# core.net
KiCad netlist of a schematic drawn in Altium Designer
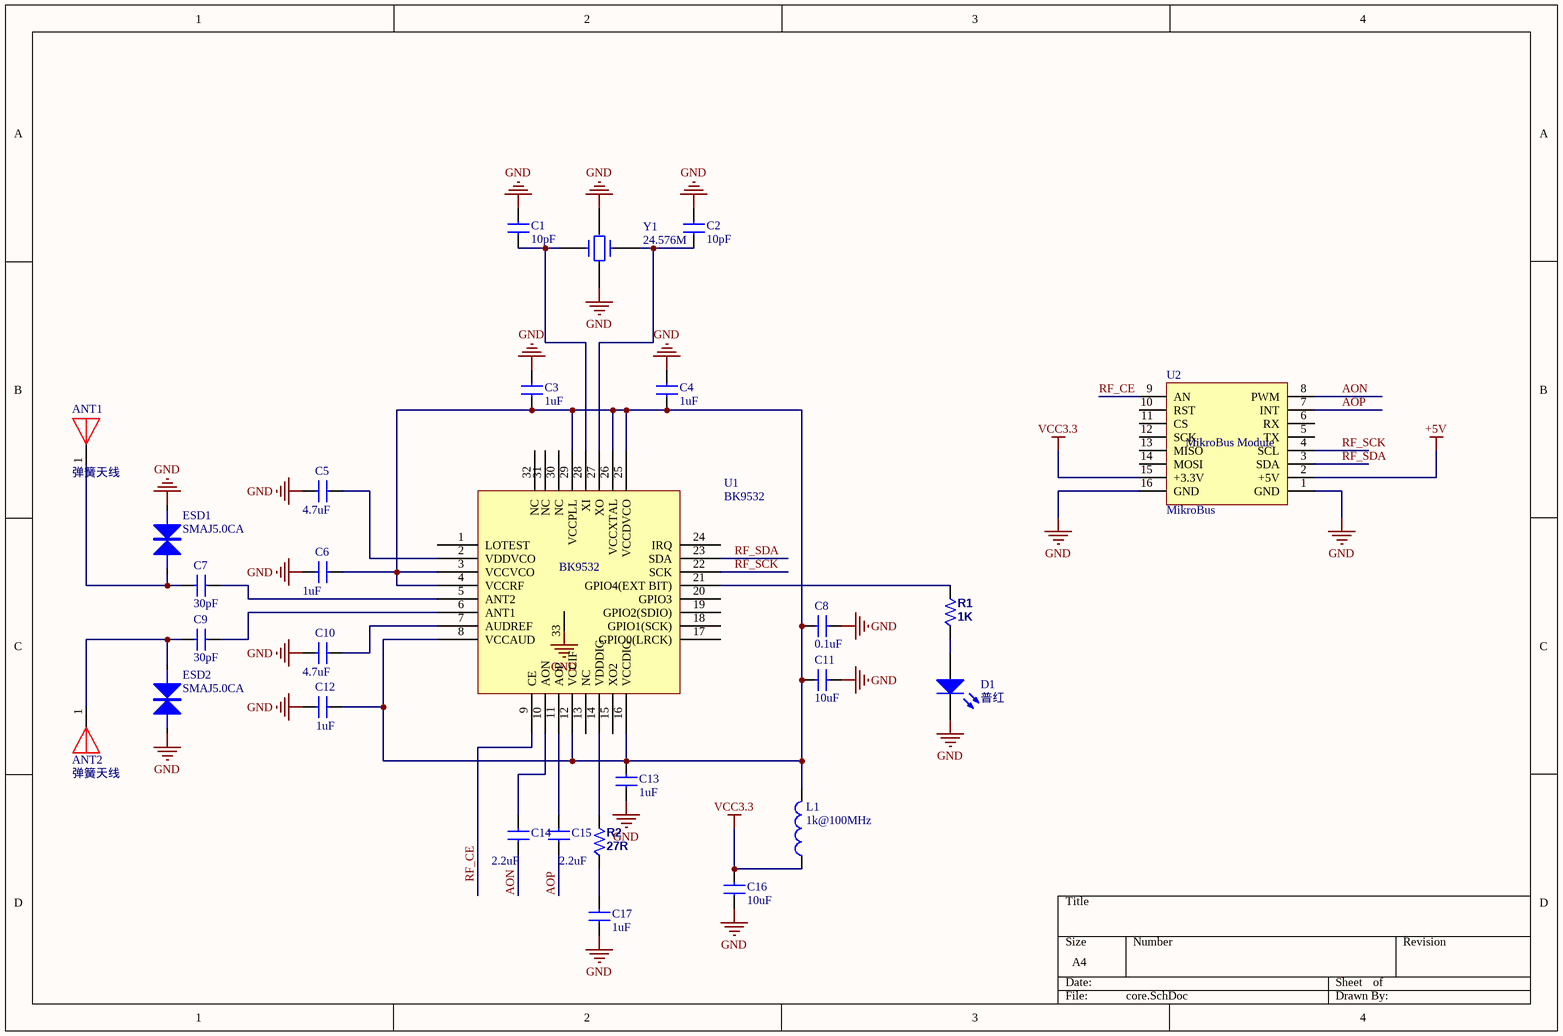
[diagram p0: core.SchDoc]

(export (version "E")
  (design (tool "Eeschema 10.0.6"))
  (components
    (comp (ref "ANT1")
      (value "弹簧天线")
      (footprint "ANT")
      (description "ANT")
      (libsource (lib "二极管") (part "ANT"))
    )
    (comp (ref "ANT2")
      (value "弹簧天线")
      (footprint "ANT")
      (description "ANT")
      (libsource (lib "二极管") (part "ANT"))
    )
    (comp (ref "C1")
      (value "10pF")
      (footprint "C0603")
      (description "0603-10pF/50V 贴片层叠电容")
      (libsource (lib "兰格封装") (part "CAP 0603-10pF/50V"))
    )
    (comp (ref "C2")
      (value "10pF")
      (footprint "C0603")
      (description "0603-10pF/50V 贴片层叠电容")
      (libsource (lib "兰格封装") (part "CAP 0603-10pF/50V"))
    )
    (comp (ref "C3")
      (value "1uF")
      (footprint "C0603")
      (description "0805-68pF/50V-J5%贴片层叠电容")
      (libsource (lib "兰格封装") (part "CAP 0805-68pF/50V"))
    )
    (comp (ref "C4")
      (value "1uF")
      (footprint "C0603")
      (description "0805-68pF/50V-J5%贴片层叠电容")
      (libsource (lib "兰格封装") (part "CAP 0805-68pF/50V"))
    )
    (comp (ref "C5")
      (value "4.7uF")
      (footprint "C0603")
      (description "0805-68pF/50V-J5%贴片层叠电容")
      (libsource (lib "兰格封装") (part "CAP 0805-68pF/50V"))
    )
    (comp (ref "C6")
      (value "1uF")
      (footprint "C0603")
      (description "0805-68pF/50V-J5%贴片层叠电容")
      (libsource (lib "兰格封装") (part "CAP 0805-68pF/50V"))
    )
    (comp (ref "C7")
      (value "30pF")
      (footprint "C0603")
      (description "0603-33pF/50V   贴片层叠电容")
      (libsource (lib "兰格封装") (part "CAP 0603-33pF/50V"))
    )
    (comp (ref "C8")
      (value "0.1uF")
      (footprint "C0603")
      (description "0805-68pF/50V-J5%贴片层叠电容")
      (libsource (lib "兰格封装") (part "CAP 0805-68pF/50V"))
    )
    (comp (ref "C9")
      (value "30pF")
      (footprint "C0603")
      (description "0603-33pF/50V   贴片层叠电容")
      (libsource (lib "兰格封装") (part "CAP 0603-33pF/50V"))
    )
    (comp (ref "C10")
      (value "4.7uF")
      (footprint "C0603")
      (description "0805-68pF/50V-J5%贴片层叠电容")
      (libsource (lib "兰格封装") (part "CAP 0805-68pF/50V"))
    )
    (comp (ref "C11")
      (value "10uF")
      (footprint "C0603")
      (description "0805-68pF/50V-J5%贴片层叠电容")
      (libsource (lib "兰格封装") (part "CAP 0805-68pF/50V"))
    )
    (comp (ref "C12")
      (value "1uF")
      (footprint "C0603")
      (description "0805-68pF/50V-J5%贴片层叠电容")
      (libsource (lib "兰格封装") (part "CAP 0805-68pF/50V"))
    )
    (comp (ref "C13")
      (value "1uF")
      (footprint "C0603")
      (description "0805-68pF/50V-J5%贴片层叠电容")
      (libsource (lib "兰格封装") (part "CAP 0805-68pF/50V"))
    )
    (comp (ref "C14")
      (value "2.2uF")
      (footprint "C0603")
      (description "0805-68pF/50V-J5%贴片层叠电容")
      (libsource (lib "兰格封装") (part "CAP 0805-68pF/50V"))
    )
    (comp (ref "C15")
      (value "2.2uF")
      (footprint "C0603")
      (description "0805-68pF/50V-J5%贴片层叠电容")
      (libsource (lib "兰格封装") (part "CAP 0805-68pF/50V"))
    )
    (comp (ref "C16")
      (value "10uF")
      (footprint "C0603")
      (description "0805-68pF/50V-J5%贴片层叠电容")
      (libsource (lib "兰格封装") (part "CAP 0805-68pF/50V"))
    )
    (comp (ref "C17")
      (value "1uF")
      (footprint "C0603")
      (description "0805-68pF/50V-J5%贴片层叠电容")
      (libsource (lib "兰格封装") (part "CAP 0805-68pF/50V"))
    )
    (comp (ref "D1")
      (value "普红")
      (footprint "LED 0805")
      (description "0805普亮贴片红灯")
      (libsource (lib "兰格封装") (part "LED  0805普亮贴片红灯"))
    )
    (comp (ref "ESD1")
      (value "SMAJ5.0CA")
      (footprint "SMAJ")
      (description "ESD 二极管")
      (libsource (lib "二极管") (part "ESD 防浪涌二极管"))
    )
    (comp (ref "ESD2")
      (value "SMAJ5.0CA")
      (footprint "SMAJ")
      (description "ESD 二极管")
      (libsource (lib "二极管") (part "ESD 防浪涌二极管"))
    )
    (comp (ref "L1")
      (value "1k@100MHz")
      (footprint "L0603")
      (description "磁珠")
      (libsource (lib "兰格封装") (part "电感  贴片  33UH"))
    )
    (comp (ref "R1")
      (value "1K")
      (footprint "R0603")
      (description "1206  K  5%  HS  贴片电阻")
      (libsource (lib "兰格封装") (part "RES1"))
    )
    (comp (ref "R2")
      (value "27R")
      (footprint "R0603")
      (description "1206  K  5%  HS  贴片电阻")
      (libsource (lib "兰格封装") (part "RES1"))
    )
    (comp (ref "U1")
      (value "BK9532")
      (footprint "QFN32")
      (description "QFN5x5 32")
      (libsource (lib "集成IC") (part "BK9532"))
    )
    (comp (ref "U2") (value "MikroBus") (footprint "MikroBus") (libsource (lib "集成IC") (part "MikroBus")))
    (comp (ref "Y1")
      (value "24.576M")
      (footprint "晶振   有源2520")
      (description "（未入库）24.576MHz  2520")
      (libsource (lib "晶体") (part "晶振  24.576MHz  49SMD"))
    )
  )
  (nets
    (net (code "1") (name "+5V") (class "Default")
      (node (ref "U2") (pin "2") (pinfunction "+5V_2") (pintype "passive"))
    )
    (net (code "2") (name "/AON") (class "Default")
      (node (ref "C14") (pin "1") (pinfunction "1_1") (pintype "passive"))
      (node (ref "U2") (pin "8") (pinfunction "PWM_8") (pintype "passive"))
    )
    (net (code "3") (name "/AOP") (class "Default")
      (node (ref "C15") (pin "1") (pinfunction "1_1") (pintype "passive"))
      (node (ref "U2") (pin "7") (pinfunction "INT_7") (pintype "passive"))
    )
    (net (code "4") (name "/RF_CE") (class "Default")
      (node (ref "U1") (pin "9") (pinfunction "CE_9") (pintype "passive"))
      (node (ref "U2") (pin "9") (pinfunction "AN_9") (pintype "passive"))
    )
    (net (code "5") (name "/RF_SCK") (class "Default")
      (node (ref "U1") (pin "22") (pinfunction "SCK_22") (pintype "passive"))
      (node (ref "U2") (pin "4") (pinfunction "SCL_4") (pintype "passive"))
    )
    (net (code "6") (name "/RF_SDA") (class "Default")
      (node (ref "U1") (pin "23") (pinfunction "SDA_23") (pintype "passive"))
      (node (ref "U2") (pin "3") (pinfunction "SDA_3") (pintype "passive"))
    )
    (net (code "7") (name "GND") (class "Default")
      (node (ref "C1") (pin "1") (pinfunction "1_1") (pintype "passive"))
      (node (ref "C10") (pin "1") (pinfunction "1_1") (pintype "passive"))
      (node (ref "C11") (pin "1") (pinfunction "1_1") (pintype "passive"))
      (node (ref "C12") (pin "1") (pinfunction "1_1") (pintype "passive"))
      (node (ref "C13") (pin "1") (pinfunction "1_1") (pintype "passive"))
      (node (ref "C16") (pin "1") (pinfunction "1_1") (pintype "passive"))
      (node (ref "C17") (pin "1") (pinfunction "1_1") (pintype "passive"))
      (node (ref "C2") (pin "1") (pinfunction "1_1") (pintype "passive"))
      (node (ref "C3") (pin "2") (pinfunction "2_2") (pintype "passive"))
      (node (ref "C4") (pin "2") (pinfunction "2_2") (pintype "passive"))
      (node (ref "C5") (pin "1") (pinfunction "1_1") (pintype "passive"))
      (node (ref "C6") (pin "1") (pinfunction "1_1") (pintype "passive"))
      (node (ref "C8") (pin "1") (pinfunction "1_1") (pintype "passive"))
      (node (ref "D1") (pin "2") (pinfunction "K_2") (pintype "passive"))
      (node (ref "ESD1") (pin "1") (pinfunction "1_1") (pintype "passive"))
      (node (ref "ESD2") (pin "1") (pinfunction "1_1") (pintype "passive"))
      (node (ref "U1") (pin "33") (pintype "passive"))
      (node (ref "U2") (pin "1") (pinfunction "GND_1") (pintype "passive"))
      (node (ref "U2") (pin "16") (pinfunction "GND_16") (pintype "passive"))
      (node (ref "Y1") (pin "2") (pinfunction "2_2") (pintype "passive"))
      (node (ref "Y1") (pin "4") (pinfunction "4_4") (pintype "passive"))
    )
    (net (code "8") (name "Net-(ANT1-Pad1)") (class "Default")
      (node (ref "ANT1") (pin "1") (pinfunction "1_1") (pintype "passive"))
      (node (ref "C7") (pin "1") (pinfunction "1_1") (pintype "passive"))
      (node (ref "ESD1") (pin "2") (pinfunction "2_2") (pintype "passive"))
    )
    (net (code "9") (name "Net-(ANT2-Pad1)") (class "Default")
      (node (ref "ANT2") (pin "1") (pinfunction "1_1") (pintype "passive"))
      (node (ref "C9") (pin "1") (pinfunction "1_1") (pintype "passive"))
      (node (ref "ESD2") (pin "2") (pinfunction "2_2") (pintype "passive"))
    )
    (net (code "10") (name "Net-(C17-Pad2)") (class "Default")
      (node (ref "C17") (pin "2") (pinfunction "2_2") (pintype "passive"))
      (node (ref "R2") (pin "1") (pintype "passive"))
    )
    (net (code "11") (name "Net-(D1-A)") (class "Default")
      (node (ref "D1") (pin "1") (pinfunction "A_1") (pintype "passive"))
      (node (ref "R1") (pin "1") (pintype "passive"))
    )
    (net (code "12") (name "Net-(U1-ANT1)") (class "Default")
      (node (ref "C9") (pin "2") (pinfunction "2_2") (pintype "passive"))
      (node (ref "U1") (pin "6") (pinfunction "ANT1_6") (pintype "passive"))
    )
    (net (code "13") (name "Net-(U1-ANT2)") (class "Default")
      (node (ref "C7") (pin "2") (pinfunction "2_2") (pintype "passive"))
      (node (ref "U1") (pin "5") (pinfunction "ANT2_5") (pintype "passive"))
    )
    (net (code "14") (name "Net-(U1-AON)") (class "Default")
      (node (ref "C14") (pin "2") (pinfunction "2_2") (pintype "passive"))
      (node (ref "U1") (pin "10") (pinfunction "AON_10") (pintype "passive"))
    )
    (net (code "15") (name "Net-(U1-AOP)") (class "Default")
      (node (ref "C15") (pin "2") (pinfunction "2_2") (pintype "passive"))
      (node (ref "U1") (pin "11") (pinfunction "AOP_11") (pintype "passive"))
    )
    (net (code "16") (name "Net-(U1-AUDREF)") (class "Default")
      (node (ref "C10") (pin "2") (pinfunction "2_2") (pintype "passive"))
      (node (ref "U1") (pin "7") (pinfunction "AUDREF_7") (pintype "passive"))
    )
    (net (code "17") (name "Net-(U1-GPIO4(EXT_BIT))") (class "Default")
      (node (ref "R1") (pin "2") (pintype "passive"))
      (node (ref "U1") (pin "21") (pinfunction "GPIO4(EXT_BIT)_21") (pintype "passive"))
    )
    (net (code "18") (name "Net-(U1-VCCAUD)") (class "Default")
      (node (ref "C11") (pin "2") (pinfunction "2_2") (pintype "passive"))
      (node (ref "C12") (pin "2") (pinfunction "2_2") (pintype "passive"))
      (node (ref "C13") (pin "2") (pinfunction "2_2") (pintype "passive"))
      (node (ref "C3") (pin "1") (pinfunction "1_1") (pintype "passive"))
      (node (ref "C4") (pin "1") (pinfunction "1_1") (pintype "passive"))
      (node (ref "C6") (pin "2") (pinfunction "2_2") (pintype "passive"))
      (node (ref "C8") (pin "2") (pinfunction "2_2") (pintype "passive"))
      (node (ref "L1") (pin "2") (pinfunction "2_2") (pintype "passive"))
      (node (ref "U1") (pin "12") (pinfunction "VCCIF_12") (pintype "passive"))
      (node (ref "U1") (pin "16") (pinfunction "VCCDIG_16") (pintype "passive"))
      (node (ref "U1") (pin "25") (pinfunction "VCCDVCO_25") (pintype "passive"))
      (node (ref "U1") (pin "26") (pinfunction "VCCXTAL_26") (pintype "passive"))
      (node (ref "U1") (pin "29") (pinfunction "VCCPLL_29") (pintype "passive"))
      (node (ref "U1") (pin "3") (pinfunction "VCCVCO_3") (pintype "passive"))
      (node (ref "U1") (pin "4") (pinfunction "VCCRF_4") (pintype "passive"))
      (node (ref "U1") (pin "8") (pinfunction "VCCAUD_8") (pintype "passive"))
    )
    (net (code "19") (name "Net-(U1-VDDDIG)") (class "Default")
      (node (ref "R2") (pin "2") (pintype "passive"))
      (node (ref "U1") (pin "14") (pinfunction "VDDDIG_14") (pintype "passive"))
    )
    (net (code "20") (name "Net-(U1-VDDVCO)") (class "Default")
      (node (ref "C5") (pin "2") (pinfunction "2_2") (pintype "passive"))
      (node (ref "U1") (pin "2") (pinfunction "VDDVCO_2") (pintype "passive"))
    )
    (net (code "21") (name "Net-(U1-XI)") (class "Default")
      (node (ref "C1") (pin "2") (pinfunction "2_2") (pintype "passive"))
      (node (ref "U1") (pin "28") (pinfunction "XI_28") (pintype "passive"))
      (node (ref "Y1") (pin "1") (pinfunction "1_1") (pintype "passive"))
    )
    (net (code "22") (name "Net-(U1-XO)") (class "Default")
      (node (ref "C2") (pin "2") (pinfunction "2_2") (pintype "passive"))
      (node (ref "U1") (pin "27") (pinfunction "XO_27") (pintype "passive"))
      (node (ref "Y1") (pin "3") (pinfunction "3_3") (pintype "passive"))
    )
    (net (code "23") (name "VCC3.3") (class "Default")
      (node (ref "C16") (pin "2") (pinfunction "2_2") (pintype "passive"))
      (node (ref "L1") (pin "1") (pinfunction "1_1") (pintype "passive"))
      (node (ref "U2") (pin "15") (pinfunction "+3.3V_15") (pintype "passive"))
    )
    (net (code "24") (name "unconnected-(U1-GPIO0(LRCK)-Pad17)") (class "Default")
      (node (ref "U1") (pin "17") (pinfunction "GPIO0(LRCK)_17") (pintype "passive"))
    )
    (net (code "25") (name "unconnected-(U1-GPIO1(SCK)-Pad18)") (class "Default")
      (node (ref "U1") (pin "18") (pinfunction "GPIO1(SCK)_18") (pintype "passive"))
    )
    (net (code "26") (name "unconnected-(U1-GPIO2(SDIO)-Pad19)") (class "Default")
      (node (ref "U1") (pin "19") (pinfunction "GPIO2(SDIO)_19") (pintype "passive"))
    )
    (net (code "27") (name "unconnected-(U1-GPIO3-Pad20)") (class "Default")
      (node (ref "U1") (pin "20") (pinfunction "GPIO3_20") (pintype "passive"))
    )
    (net (code "28") (name "unconnected-(U1-IRQ-Pad24)") (class "Default")
      (node (ref "U1") (pin "24") (pinfunction "IRQ_24") (pintype "passive"))
    )
    (net (code "29") (name "unconnected-(U1-LOTEST-Pad1)") (class "Default")
      (node (ref "U1") (pin "1") (pinfunction "LOTEST_1") (pintype "passive"))
    )
    (net (code "30") (name "unconnected-(U1-NC-Pad13)") (class "Default")
      (node (ref "U1") (pin "13") (pinfunction "NC_13") (pintype "passive"))
    )
    (net (code "31") (name "unconnected-(U1-NC-Pad30)") (class "Default")
      (node (ref "U1") (pin "30") (pinfunction "NC_30") (pintype "passive"))
    )
    (net (code "32") (name "unconnected-(U1-NC-Pad31)") (class "Default")
      (node (ref "U1") (pin "31") (pinfunction "NC_31") (pintype "passive"))
    )
    (net (code "33") (name "unconnected-(U1-NC-Pad32)") (class "Default")
      (node (ref "U1") (pin "32") (pinfunction "NC_32") (pintype "passive"))
    )
    (net (code "34") (name "unconnected-(U1-XO2-Pad15)") (class "Default")
      (node (ref "U1") (pin "15") (pinfunction "XO2_15") (pintype "passive"))
    )
    (net (code "35") (name "unconnected-(U2-CS-Pad11)") (class "Default")
      (node (ref "U2") (pin "11") (pinfunction "CS_11") (pintype "passive"))
    )
    (net (code "36") (name "unconnected-(U2-MISO-Pad13)") (class "Default")
      (node (ref "U2") (pin "13") (pinfunction "MISO_13") (pintype "passive"))
    )
    (net (code "37") (name "unconnected-(U2-MOSI-Pad14)") (class "Default")
      (node (ref "U2") (pin "14") (pinfunction "MOSI_14") (pintype "passive"))
    )
    (net (code "38") (name "unconnected-(U2-RST-Pad10)") (class "Default")
      (node (ref "U2") (pin "10") (pinfunction "RST_10") (pintype "passive"))
    )
    (net (code "39") (name "unconnected-(U2-RX-Pad6)") (class "Default")
      (node (ref "U2") (pin "6") (pinfunction "RX_6") (pintype "passive"))
    )
    (net (code "40") (name "unconnected-(U2-SCK-Pad12)") (class "Default")
      (node (ref "U2") (pin "12") (pinfunction "SCK_12") (pintype "passive"))
    )
    (net (code "41") (name "unconnected-(U2-TX-Pad5)") (class "Default")
      (node (ref "U2") (pin "5") (pinfunction "TX_5") (pintype "passive"))
    )
  )
)
